# 464342_21-005_3_8.net
KiCad netlist of a schematic drawn in Altium Designer
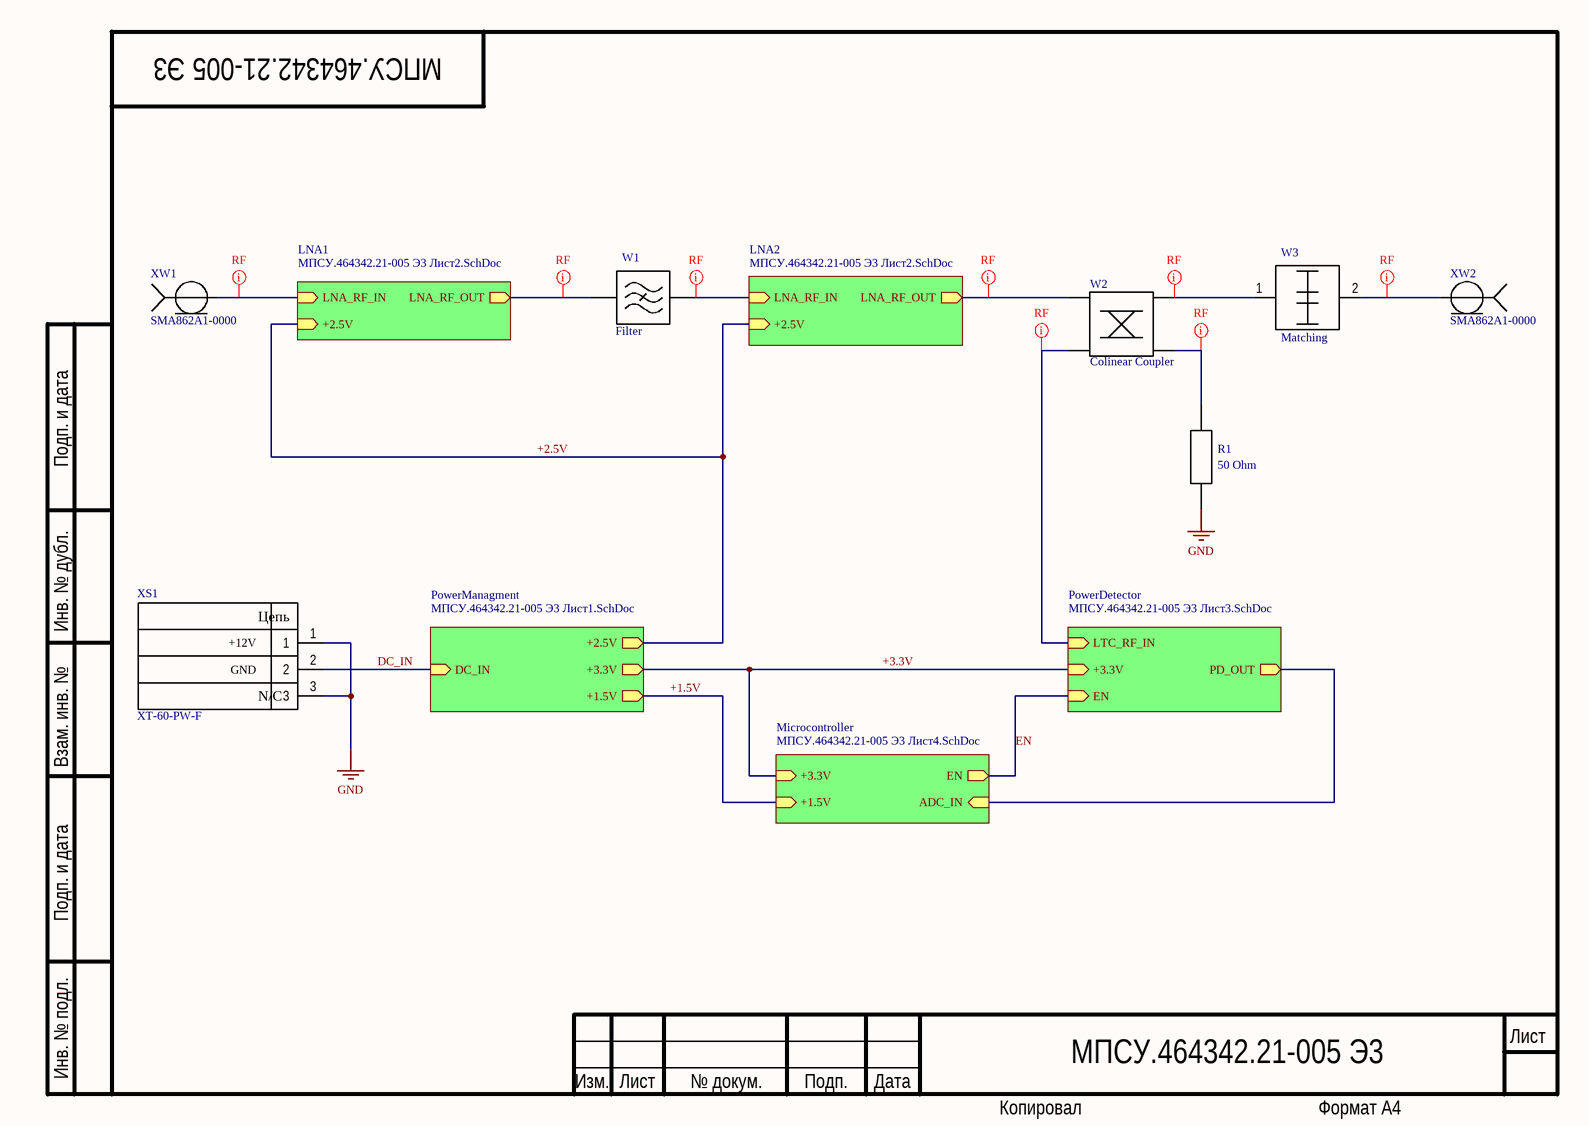
[diagram p0: МПСУ.464342.21-005 Э3 Лист8.SchDoc]

(export (version "E")
  (design (tool "Eeschema 10.0.6"))
  (components
    (comp (ref "R1")
      (value "50 Ohm")
      (footprint "RESC160X80X60L30N")
      (description "Resistor, generic")
      (libsource (lib "Discrete") (part "Resistor"))
    )
    (comp (ref "W1")
      (value "Filter")
      (footprint "MFilter8_5G")
      (libsource (lib "Microstrip") (part "Filter 8.5G"))
    )
    (comp (ref "W2")
      (value "Colinear Coupler")
      (footprint "CLCoupler")
      (description "Coupler 40 dB, diel RO4003 0.5 oz ED 20 mil")
      (libsource (lib "Microstrip") (part "CLCoupler"))
    )
    (comp (ref "W3")
      (value "Matching")
      (footprint "MATCHING_MAIN_OUT")
      (libsource (lib "Microstrip") (part "Matching_1"))
    )
    (comp (ref "XS1")
      (value "XT-60-PW-F")
      (footprint "Connectors:XT-60-PW-F")
      (description "Header, Right-angle, 2x1")
      (fields (field (name "NET2") "GND") (field (name "NET1") "+12V"))
      (libsource (lib "Connectors") (part "XT-60-PW-F"))
    )
    (comp (ref "XW1")
      (value "SMA862A1-0000")
      (footprint "SMA862A1-0000")
      (description "SMA Jack For Panel Receptacle 50Ohm JYEBAO")
      (libsource (lib "Connectors") (part "SMA862A1-0000"))
    )
    (comp (ref "XW2")
      (value "SMA862A1-0000")
      (footprint "SMA862A1-0000")
      (description "SMA Jack For Panel Receptacle 50Ohm JYEBAO")
      (libsource (lib "Connectors") (part "SMA862A1-0000"))
    )
  )
  (nets
    (net (code "4") (name "/DC_IN") (class "Default")
      (node (ref "XS1") (pin "2") (pinfunction "2_2") (pintype "passive"))
    )
    (net (code "6") (name "/LNA_RF_IN") (class "Default")
      (node (ref "W1") (pin "2") (pinfunction "2_2") (pintype "passive"))
    )
    (net (code "7") (name "/LNA_RF_IN_1") (class "Default")
      (node (ref "XW1") (pin "1") (pinfunction "1_1") (pintype "passive"))
    )
    (net (code "8") (name "/LNA_RF_OUT") (class "Default")
      (node (ref "W2") (pin "1") (pinfunction "1_1") (pintype "passive"))
    )
    (net (code "9") (name "/LNA_RF_OUT_1") (class "Default")
      (node (ref "W1") (pin "1") (pinfunction "1_1") (pintype "passive"))
    )
    (net (code "10") (name "/LTC_RF_IN") (class "Default")
      (node (ref "W2") (pin "4") (pinfunction "4_4") (pintype "passive"))
    )
    (net (code "12") (name "GND") (class "Default")
      (node (ref "R1") (pin "1") (pinfunction "1_1") (pintype "passive"))
      (node (ref "XS1") (pin "1") (pinfunction "1_1") (pintype "passive"))
      (node (ref "XS1") (pin "3") (pinfunction "3_3") (pintype "passive"))
    )
    (net (code "13") (name "Net-(R1-Pad2)") (class "Default")
      (node (ref "R1") (pin "2") (pinfunction "2_2") (pintype "passive"))
      (node (ref "W2") (pin "3") (pinfunction "3_3") (pintype "passive"))
    )
    (net (code "14") (name "Net-(W2-Pad2)") (class "Default")
      (node (ref "W2") (pin "2") (pinfunction "2_2") (pintype "passive"))
      (node (ref "W3") (pin "1") (pinfunction "1_1") (pintype "passive"))
    )
    (net (code "15") (name "Net-(W3-Pad2)") (class "Default")
      (node (ref "W3") (pin "2") (pinfunction "2_2") (pintype "passive"))
      (node (ref "XW2") (pin "1") (pinfunction "1_1") (pintype "passive"))
    )
  )
)
